# BQ25798.net
KiCad netlist of a schematic drawn in EAGLE
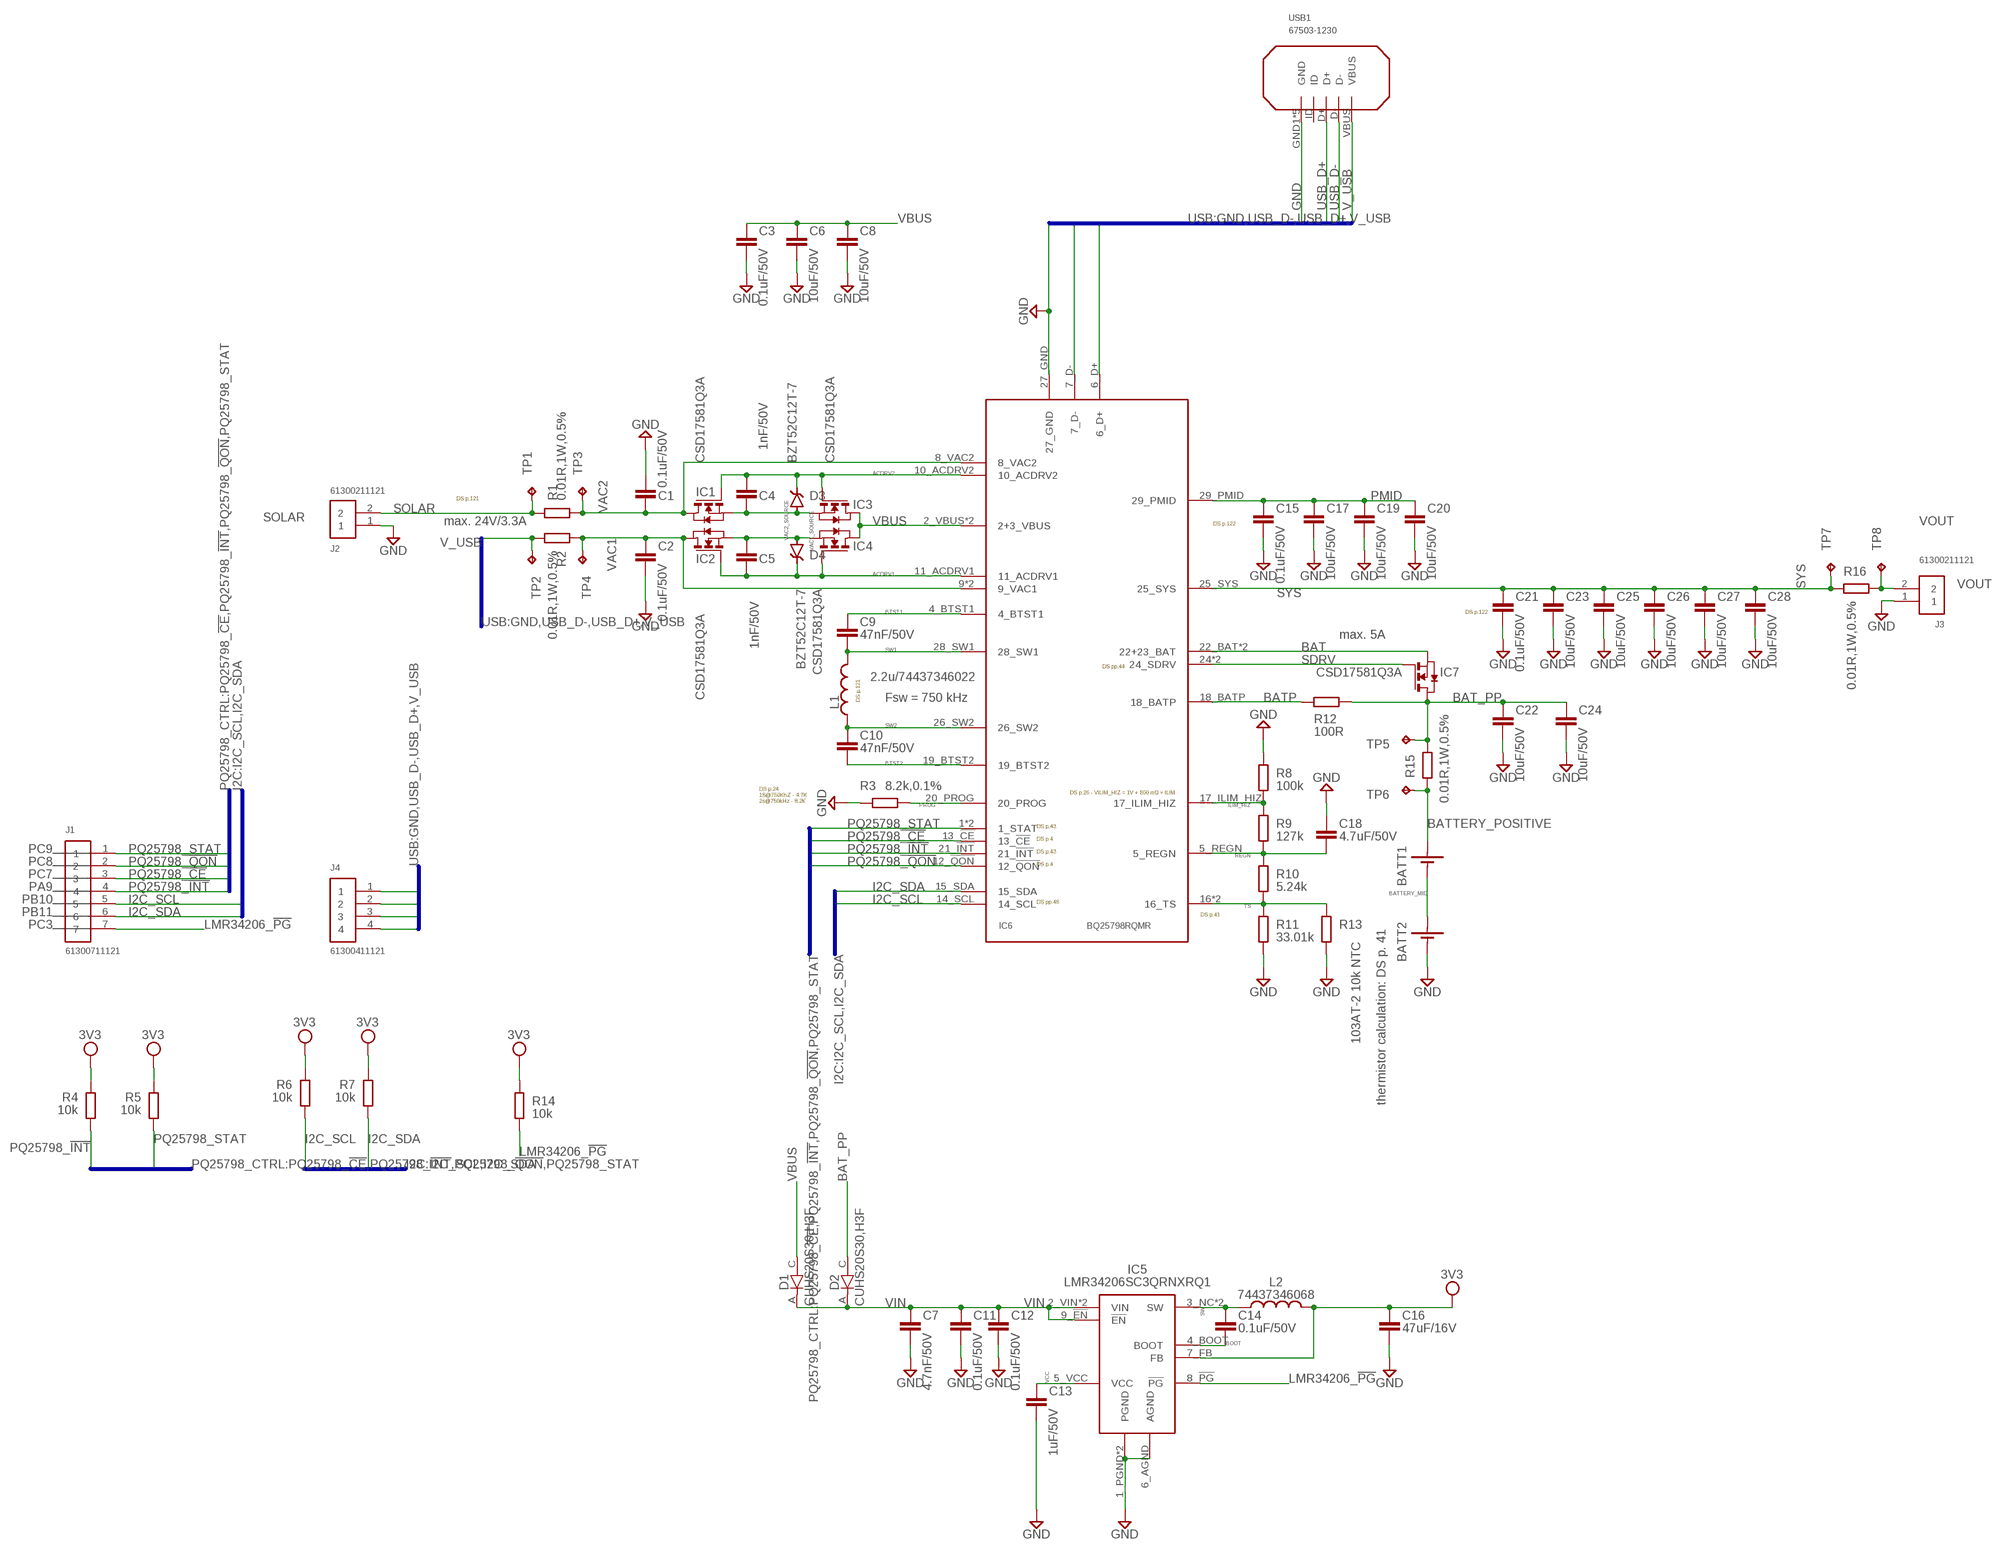
[diagram p0: schematic, sheet 1]

(export (version "E")
  (design (tool "Eeschema 10.0.6"))
  (components
    (comp (ref "BATT1")
      (value "BATTERY")
      (footprint "eagle-import:TH")
      (libsource (lib "eagle-import") (part "BATTERY"))
    )
    (comp (ref "BATT2")
      (value "BATTERY")
      (footprint "eagle-import:TH")
      (libsource (lib "eagle-import") (part "BATTERY"))
    )
    (comp (ref "C1")
      (value "0.1uF/50V")
      (footprint "eagle-import:C0402")
      (libsource (lib "eagle-import") (part "C-EUC0402"))
    )
    (comp (ref "C2")
      (value "0.1uF/50V")
      (footprint "eagle-import:C0402")
      (libsource (lib "eagle-import") (part "C-EUC0402"))
    )
    (comp (ref "C3")
      (value "0.1uF/50V")
      (footprint "eagle-import:C0402")
      (libsource (lib "eagle-import") (part "C-EUC0402"))
    )
    (comp (ref "C4")
      (value "1nF/50V")
      (footprint "eagle-import:C0402")
      (libsource (lib "eagle-import") (part "C-EUC0402"))
    )
    (comp (ref "C5")
      (value "1nF/50V")
      (footprint "eagle-import:C0402")
      (libsource (lib "eagle-import") (part "C-EUC0402"))
    )
    (comp (ref "C6")
      (value "10uF/50V")
      (footprint "eagle-import:C0805")
      (libsource (lib "eagle-import") (part "C-EUC0805"))
    )
    (comp (ref "C7")
      (value "4.7nF/50V")
      (footprint "eagle-import:C0805")
      (libsource (lib "eagle-import") (part "C-EUC0805"))
    )
    (comp (ref "C8")
      (value "10uF/50V")
      (footprint "eagle-import:C0805")
      (libsource (lib "eagle-import") (part "C-EUC0805"))
    )
    (comp (ref "C9")
      (value "47nF/50V")
      (footprint "eagle-import:C0603")
      (libsource (lib "eagle-import") (part "C-EUC0603"))
    )
    (comp (ref "C10")
      (value "47nF/50V")
      (footprint "eagle-import:C0603")
      (libsource (lib "eagle-import") (part "C-EUC0603"))
    )
    (comp (ref "C11")
      (value "0.1uF/50V")
      (footprint "eagle-import:C0402")
      (libsource (lib "eagle-import") (part "C-EUC0402"))
    )
    (comp (ref "C12")
      (value "0.1uF/50V")
      (footprint "eagle-import:C0402")
      (libsource (lib "eagle-import") (part "C-EUC0402"))
    )
    (comp (ref "C13")
      (value "1uF/50V")
      (footprint "eagle-import:C0805")
      (libsource (lib "eagle-import") (part "C-EUC0805"))
    )
    (comp (ref "C14")
      (value "0.1uF/50V")
      (footprint "eagle-import:C0402")
      (libsource (lib "eagle-import") (part "C-EUC0402"))
    )
    (comp (ref "C15")
      (value "0.1uF/50V")
      (footprint "eagle-import:C0402")
      (libsource (lib "eagle-import") (part "C-EUC0402"))
    )
    (comp (ref "C16")
      (value "47uF/16V")
      (footprint "eagle-import:C1206")
      (libsource (lib "eagle-import") (part "C-EUC1206"))
    )
    (comp (ref "C17")
      (value "10uF/50V")
      (footprint "eagle-import:C0805")
      (libsource (lib "eagle-import") (part "C-EUC0805"))
    )
    (comp (ref "C18")
      (value "4.7uF/50V")
      (footprint "eagle-import:C0603")
      (libsource (lib "eagle-import") (part "C-EUC0603"))
    )
    (comp (ref "C19")
      (value "10uF/50V")
      (footprint "eagle-import:C0805")
      (libsource (lib "eagle-import") (part "C-EUC0805"))
    )
    (comp (ref "C20")
      (value "10uF/50V")
      (footprint "eagle-import:C0805")
      (libsource (lib "eagle-import") (part "C-EUC0805"))
    )
    (comp (ref "C21")
      (value "0.1uF/50V")
      (footprint "eagle-import:C0402")
      (libsource (lib "eagle-import") (part "C-EUC0402"))
    )
    (comp (ref "C22")
      (value "10uF/50V")
      (footprint "eagle-import:C0805")
      (libsource (lib "eagle-import") (part "C-EUC0805"))
    )
    (comp (ref "C23")
      (value "10uF/50V")
      (footprint "eagle-import:C0805")
      (libsource (lib "eagle-import") (part "C-EUC0805"))
    )
    (comp (ref "C24")
      (value "10uF/50V")
      (footprint "eagle-import:C0805")
      (libsource (lib "eagle-import") (part "C-EUC0805"))
    )
    (comp (ref "C25")
      (value "10uF/50V")
      (footprint "eagle-import:C0805")
      (libsource (lib "eagle-import") (part "C-EUC0805"))
    )
    (comp (ref "C26")
      (value "10uF/50V")
      (footprint "eagle-import:C0805")
      (libsource (lib "eagle-import") (part "C-EUC0805"))
    )
    (comp (ref "C27")
      (value "10uF/50V")
      (footprint "eagle-import:C0805")
      (libsource (lib "eagle-import") (part "C-EUC0805"))
    )
    (comp (ref "C28")
      (value "10uF/50V")
      (footprint "eagle-import:C0805")
      (libsource (lib "eagle-import") (part "C-EUC0805"))
    )
    (comp (ref "D1")
      (value "CUHS20S30,H3F")
      (footprint "eagle-import:US2H")
      (libsource (lib "eagle-import") (part "CUHS20S30"))
    )
    (comp (ref "D2")
      (value "CUHS20S30,H3F")
      (footprint "eagle-import:US2H")
      (libsource (lib "eagle-import") (part "CUHS20S30"))
    )
    (comp (ref "D3")
      (value "BZT52C12T-7")
      (footprint "eagle-import:SOD-523-2")
      (libsource (lib "eagle-import") (part "BZT52C2V0T"))
    )
    (comp (ref "D4")
      (value "BZT52C12T-7")
      (footprint "eagle-import:SOD-523-2")
      (libsource (lib "eagle-import") (part "BZT52C2V0T"))
    )
    (comp (ref "IC1")
      (value "CSD17581Q3A")
      (footprint "eagle-import:PQFN-12")
      (libsource (lib "eagle-import") (part "CSD17581Q3A"))
    )
    (comp (ref "IC2")
      (value "CSD17581Q3A")
      (footprint "eagle-import:PQFN-12")
      (libsource (lib "eagle-import") (part "CSD17581Q3A"))
    )
    (comp (ref "IC3")
      (value "CSD17581Q3A")
      (footprint "eagle-import:PQFN-12")
      (libsource (lib "eagle-import") (part "CSD17581Q3A"))
    )
    (comp (ref "IC4")
      (value "CSD17581Q3A")
      (footprint "eagle-import:PQFN-12")
      (libsource (lib "eagle-import") (part "CSD17581Q3A"))
    )
    (comp (ref "IC5")
      (value "LMR34206SC3QRNXRQ1")
      (footprint "eagle-import:VQFN-HR(12)")
      (libsource (lib "eagle-import") (part "LMR34206-Q1"))
    )
    (comp (ref "IC6")
      (value "BQ25798RQMR")
      (footprint "eagle-import:QFN29")
      (libsource (lib "eagle-import") (part "BQ25798"))
    )
    (comp (ref "IC7")
      (value "CSD17581Q3A")
      (footprint "eagle-import:PQFN-12")
      (libsource (lib "eagle-import") (part "CSD17581Q3A"))
    )
    (comp (ref "J1")
      (value "61300711121")
      (footprint "eagle-import:61300711121")
      (fields
        (field (name "DIGI_KEY_PART_NUMBER") "732-5320-ND")
        (field (name "MANUFACTURER") "Wurth Electronics Inc.")
        (field (name "CREATED_BY") "PCBLayout.com")
      )
      (libsource (lib "eagle-import") (part "61300711121"))
    )
    (comp (ref "J2")
      (value "61300211121")
      (footprint "eagle-import:61300211121")
      (fields
        (field (name "DIGI_KEY_PART_NUMBER") "732-5315-ND")
        (field (name "MANUFACTURER") "Wurth Electronics Inc.")
        (field (name "CREATED_BY") "PCBLayout.com")
      )
      (libsource (lib "eagle-import") (part "61300211121"))
    )
    (comp (ref "J3")
      (value "61300211121")
      (footprint "eagle-import:61300211121")
      (fields
        (field (name "DIGI_KEY_PART_NUMBER") "732-5315-ND")
        (field (name "MANUFACTURER") "Wurth Electronics Inc.")
        (field (name "CREATED_BY") "PCBLayout.com")
      )
      (libsource (lib "eagle-import") (part "61300211121"))
    )
    (comp (ref "J4")
      (value "61300411121")
      (footprint "eagle-import:61300411121")
      (fields
        (field (name "DIGI_KEY_PART_NUMBER") "732-5317-ND")
        (field (name "MANUFACTURER") "Wurth Electronics Inc.")
        (field (name "CREATED_BY") "PCBLayout.com")
      )
      (libsource (lib "eagle-import") (part "61300411121"))
    )
    (comp (ref "L1")
      (value "2.2u/74437346022")
      (footprint "eagle-import:SMD")
      (libsource (lib "eagle-import") (part "74437346022"))
    )
    (comp (ref "L2")
      (value "74437346068")
      (footprint "eagle-import:SMD")
      (libsource (lib "eagle-import") (part "74437346022"))
    )
    (comp (ref "R1")
      (value "0.01R,1W,0.5%")
      (footprint "eagle-import:R1206")
      (libsource (lib "eagle-import") (part "R-EU_R1206"))
    )
    (comp (ref "R2")
      (value "0.01R,1W,0.5%")
      (footprint "eagle-import:R1206")
      (libsource (lib "eagle-import") (part "R-EU_R1206"))
    )
    (comp (ref "R3")
      (value "8.2k,0.1%")
      (footprint "eagle-import:R0603")
      (libsource (lib "eagle-import") (part "R-EU_R0603"))
    )
    (comp (ref "R4")
      (value "10k")
      (footprint "eagle-import:R0402")
      (libsource (lib "eagle-import") (part "R-EU_R0402"))
    )
    (comp (ref "R5")
      (value "10k")
      (footprint "eagle-import:R0402")
      (libsource (lib "eagle-import") (part "R-EU_R0402"))
    )
    (comp (ref "R6")
      (value "10k")
      (footprint "eagle-import:R0402")
      (libsource (lib "eagle-import") (part "R-EU_R0402"))
    )
    (comp (ref "R7")
      (value "10k")
      (footprint "eagle-import:R0402")
      (libsource (lib "eagle-import") (part "R-EU_R0402"))
    )
    (comp (ref "R8")
      (value "100k")
      (footprint "eagle-import:R0402")
      (libsource (lib "eagle-import") (part "R-EU_R0402"))
    )
    (comp (ref "R9")
      (value "127k")
      (footprint "eagle-import:R0402")
      (libsource (lib "eagle-import") (part "R-EU_R0402"))
    )
    (comp (ref "R10")
      (value "5.24k")
      (footprint "eagle-import:R0402")
      (libsource (lib "eagle-import") (part "R-EU_R0402"))
    )
    (comp (ref "R11")
      (value "33.01k")
      (footprint "eagle-import:R0402")
      (libsource (lib "eagle-import") (part "R-EU_R0402"))
    )
    (comp (ref "R12")
      (value "100R")
      (footprint "eagle-import:R0603")
      (libsource (lib "eagle-import") (part "R-EU_R0603"))
    )
    (comp (ref "R13")
      (value "103AT-2 10k NTC")
      (footprint "eagle-import:V526-0")
      (libsource (lib "eagle-import") (part "R-EU_V526-0"))
    )
    (comp (ref "R14")
      (value "10k")
      (footprint "eagle-import:R0402")
      (libsource (lib "eagle-import") (part "R-EU_R0402"))
    )
    (comp (ref "R15")
      (value "0.01R,1W,0.5%")
      (footprint "eagle-import:R1206")
      (libsource (lib "eagle-import") (part "R-EU_R1206"))
    )
    (comp (ref "R16")
      (value "0.01R,1W,0.5%")
      (footprint "eagle-import:R1206")
      (libsource (lib "eagle-import") (part "R-EU_R1206"))
    )
    (comp (ref "TP1")
      (value "TPPAD1-13")
      (footprint "eagle-import:P1-13")
      (libsource (lib "eagle-import") (part "TPPAD1-13"))
    )
    (comp (ref "TP2")
      (value "TPPAD1-13")
      (footprint "eagle-import:P1-13")
      (libsource (lib "eagle-import") (part "TPPAD1-13"))
    )
    (comp (ref "TP3")
      (value "TPPAD1-13")
      (footprint "eagle-import:P1-13")
      (libsource (lib "eagle-import") (part "TPPAD1-13"))
    )
    (comp (ref "TP4")
      (value "TPPAD1-13")
      (footprint "eagle-import:P1-13")
      (libsource (lib "eagle-import") (part "TPPAD1-13"))
    )
    (comp (ref "TP5")
      (value "TPPAD1-13")
      (footprint "eagle-import:P1-13")
      (libsource (lib "eagle-import") (part "TPPAD1-13"))
    )
    (comp (ref "TP6")
      (value "TPPAD1-13")
      (footprint "eagle-import:P1-13")
      (libsource (lib "eagle-import") (part "TPPAD1-13"))
    )
    (comp (ref "TP7")
      (value "TPPAD1-13")
      (footprint "eagle-import:P1-13")
      (libsource (lib "eagle-import") (part "TPPAD1-13"))
    )
    (comp (ref "TP8")
      (value "TPPAD1-13")
      (footprint "eagle-import:P1-13")
      (libsource (lib "eagle-import") (part "TPPAD1-13"))
    )
    (comp (ref "USB1")
      (value "67503-1230")
      (footprint "eagle-import:SMT")
      (libsource (lib "eagle-import") (part "MX-67503-1230"))
    )
  )
  (nets
    (net (code "4") (name "/ACDRV1") (class "Default")
      (node (ref "C5") (pin "2") (pinfunction "2_2") (pintype "passive"))
      (node (ref "D4") (pin "C") (pinfunction "C_C") (pintype "passive"))
      (node (ref "IC2") (pin "4_G") (pinfunction "G_4_G") (pintype "passive"))
      (node (ref "IC4") (pin "4_G") (pinfunction "G_4_G") (pintype "passive"))
      (node (ref "IC6") (pin "11_ACDRV1") (pinfunction "11_ACDRV1_11_ACDRV1") (pintype "output"))
    )
    (net (code "5") (name "/ACDRV2") (class "Default")
      (node (ref "C4") (pin "1") (pinfunction "1_1") (pintype "passive"))
      (node (ref "D3") (pin "C") (pinfunction "C_C") (pintype "passive"))
      (node (ref "IC1") (pin "4_G") (pinfunction "G_4_G") (pintype "passive"))
      (node (ref "IC3") (pin "4_G") (pinfunction "G_4_G") (pintype "passive"))
      (node (ref "IC6") (pin "10_ACDRV2") (pinfunction "10_ACDRV2_10_ACDRV2") (pintype "output"))
    )
    (net (code "6") (name "/BAT") (class "Default")
      (node (ref "IC6") (pin "22_BAT") (pinfunction "22+23_BAT_22_BAT") (pintype "power_in"))
      (node (ref "IC6") (pin "23_BAT") (pinfunction "22+23_BAT_23_BAT") (pintype "power_in"))
      (node (ref "IC7") (pin "1_S") (pinfunction "S_1_S") (pintype "passive"))
      (node (ref "IC7") (pin "2_S") (pinfunction "S_2_S") (pintype "passive"))
      (node (ref "IC7") (pin "3_S") (pinfunction "S_3_S") (pintype "passive"))
    )
    (net (code "7") (name "/BATP") (class "Default")
      (node (ref "IC6") (pin "18_BATP") (pinfunction "18_BATP_18_BATP") (pintype "power_in"))
      (node (ref "R12") (pin "1") (pinfunction "1_1") (pintype "passive"))
    )
    (net (code "8") (name "/BATTERY_MID") (class "Default")
      (node (ref "BATT1") (pin "-") (pinfunction "NEG_-") (pintype "power_in"))
      (node (ref "BATT2") (pin "+") (pinfunction "POS_+") (pintype "power_in"))
    )
    (net (code "9") (name "/BATTERY_POSITIVE") (class "Default")
      (node (ref "BATT1") (pin "+") (pinfunction "POS_+") (pintype "power_in"))
      (node (ref "R15") (pin "1") (pinfunction "1_1") (pintype "passive"))
      (node (ref "TP6") (pin "TP") (pinfunction "TP_TP") (pintype "input"))
    )
    (net (code "10") (name "/BAT_PP") (class "Default")
      (node (ref "C22") (pin "1") (pinfunction "1_1") (pintype "passive"))
      (node (ref "C24") (pin "1") (pinfunction "1_1") (pintype "passive"))
      (node (ref "D2") (pin "C") (pinfunction "C_C") (pintype "bidirectional"))
      (node (ref "IC7") (pin "5_D") (pinfunction "D_5_D") (pintype "passive"))
      (node (ref "IC7") (pin "6_D") (pinfunction "D_6_D") (pintype "passive"))
      (node (ref "IC7") (pin "7_D") (pinfunction "D_7_D") (pintype "passive"))
      (node (ref "IC7") (pin "8_D") (pinfunction "D_8_D") (pintype "passive"))
      (node (ref "IC7") (pin "9_D") (pinfunction "D_9_D") (pintype "passive"))
      (node (ref "R12") (pin "2") (pinfunction "2_2") (pintype "passive"))
      (node (ref "R15") (pin "2") (pinfunction "2_2") (pintype "passive"))
      (node (ref "TP5") (pin "TP") (pinfunction "TP_TP") (pintype "input"))
    )
    (net (code "11") (name "/BOOT") (class "Default")
      (node (ref "C14") (pin "2") (pinfunction "2_2") (pintype "passive"))
      (node (ref "IC5") (pin "4_BOOT") (pinfunction "BOOT_4_BOOT") (pintype "bidirectional"))
    )
    (net (code "12") (name "/BTST1") (class "Default")
      (node (ref "C9") (pin "1") (pinfunction "1_1") (pintype "passive"))
      (node (ref "IC6") (pin "4_BTST1") (pinfunction "4_BTST1_4_BTST1") (pintype "output"))
    )
    (net (code "13") (name "/BTST2") (class "Default")
      (node (ref "C10") (pin "2") (pinfunction "2_2") (pintype "passive"))
      (node (ref "IC6") (pin "19_BTST2") (pinfunction "19_BTST2_19_BTST2") (pintype "output"))
    )
    (net (code "14") (name "/I2C_SCL") (class "Default")
      (node (ref "IC6") (pin "14_SCL") (pinfunction "14_SCL_14_SCL") (pintype "input"))
      (node (ref "J1") (pin "5") (pinfunction "5_5") (pintype "passive"))
      (node (ref "R6") (pin "1") (pinfunction "1_1") (pintype "passive"))
    )
    (net (code "15") (name "/I2C_SDA") (class "Default")
      (node (ref "IC6") (pin "15_SDA") (pinfunction "15_SDA_15_SDA") (pintype "bidirectional"))
      (node (ref "J1") (pin "6") (pinfunction "6_6") (pintype "passive"))
      (node (ref "R7") (pin "1") (pinfunction "1_1") (pintype "passive"))
    )
    (net (code "16") (name "/ILIM_HIZ") (class "Default")
      (node (ref "IC6") (pin "17_ILIM_HIZ") (pinfunction "17_ILIM_HIZ_17_ILIM_HIZ") (pintype "input"))
      (node (ref "R8") (pin "2") (pinfunction "2_2") (pintype "passive"))
      (node (ref "R9") (pin "1") (pinfunction "1_1") (pintype "passive"))
    )
    (net (code "17") (name "/LMR34206_~{PG}") (class "Default")
      (node (ref "IC5") (pin "8_!PG!") (pinfunction "~{PG}_8_!PG!") (pintype "output"))
      (node (ref "J1") (pin "7") (pinfunction "7_7") (pintype "passive"))
      (node (ref "R14") (pin "2") (pinfunction "2_2") (pintype "passive"))
    )
    (net (code "18") (name "/PMID") (class "Default")
      (node (ref "C15") (pin "1") (pinfunction "1_1") (pintype "passive"))
      (node (ref "C17") (pin "1") (pinfunction "1_1") (pintype "passive"))
      (node (ref "C19") (pin "1") (pinfunction "1_1") (pintype "passive"))
      (node (ref "C20") (pin "1") (pinfunction "1_1") (pintype "passive"))
      (node (ref "IC6") (pin "29_PMID") (pinfunction "29_PMID_29_PMID") (pintype "output"))
    )
    (net (code "19") (name "/PQ25798_STAT") (class "Default")
      (node (ref "IC6") (pin "1") (pinfunction "1_STAT_1") (pintype "output"))
      (node (ref "IC6") (pin "1_STAT") (pinfunction "1_STAT_1_STAT") (pintype "output"))
      (node (ref "J1") (pin "1") (pinfunction "1_1") (pintype "passive"))
      (node (ref "R5") (pin "1") (pinfunction "1_1") (pintype "passive"))
    )
    (net (code "20") (name "/PQ25798_~{CE}") (class "Default")
      (node (ref "IC6") (pin "13_!CE!") (pinfunction "13_~{CE}_13_!CE!") (pintype "input"))
      (node (ref "J1") (pin "3") (pinfunction "3_3") (pintype "passive"))
    )
    (net (code "21") (name "/PQ25798_~{INT}") (class "Default")
      (node (ref "IC6") (pin "21_!INT!") (pinfunction "21_~{INT}_21_!INT!") (pintype "output"))
      (node (ref "J1") (pin "4") (pinfunction "4_4") (pintype "passive"))
      (node (ref "R4") (pin "1") (pinfunction "1_1") (pintype "passive"))
    )
    (net (code "22") (name "/PQ25798_~{QON}") (class "Default")
      (node (ref "IC6") (pin "12_!QON!") (pinfunction "12_~{QON}_12_!QON!") (pintype "input"))
      (node (ref "J1") (pin "2") (pinfunction "2_2") (pintype "passive"))
    )
    (net (code "23") (name "/PROG") (class "Default")
      (node (ref "IC6") (pin "20_PROG") (pinfunction "20_PROG_20_PROG") (pintype "input"))
      (node (ref "R3") (pin "2") (pinfunction "2_2") (pintype "passive"))
    )
    (net (code "24") (name "/REGN") (class "Default")
      (node (ref "C18") (pin "2") (pinfunction "2_2") (pintype "passive"))
      (node (ref "IC6") (pin "5_REGN") (pinfunction "5_REGN_5_REGN") (pintype "output"))
      (node (ref "R10") (pin "1") (pinfunction "1_1") (pintype "passive"))
      (node (ref "R9") (pin "2") (pinfunction "2_2") (pintype "passive"))
    )
    (net (code "25") (name "/SDRV") (class "Default")
      (node (ref "IC6") (pin "24") (pinfunction "24_SDRV_24") (pintype "output"))
      (node (ref "IC6") (pin "24_SDRV") (pinfunction "24_SDRV_24_SDRV") (pintype "output"))
      (node (ref "IC7") (pin "4_G") (pinfunction "G_4_G") (pintype "passive"))
    )
    (net (code "26") (name "/SOLAR") (class "Default")
      (node (ref "J2") (pin "2") (pinfunction "2_2") (pintype "passive"))
      (node (ref "R1") (pin "1") (pinfunction "1_1") (pintype "passive"))
      (node (ref "TP1") (pin "TP") (pinfunction "TP_TP") (pintype "input"))
    )
    (net (code "27") (name "/SW") (class "Default")
      (node (ref "C14") (pin "1") (pinfunction "1_1") (pintype "passive"))
      (node (ref "IC5") (pin "12_SW") (pinfunction "SW_12_SW") (pintype "bidirectional"))
      (node (ref "IC5") (pin "3_NC") (pinfunction "SW_3_NC") (pintype "bidirectional"))
      (node (ref "L2") (pin "P$1") (pinfunction "P$1_P$1") (pintype "bidirectional"))
    )
    (net (code "28") (name "/SW1") (class "Default")
      (node (ref "C9") (pin "2") (pinfunction "2_2") (pintype "passive"))
      (node (ref "IC6") (pin "28_SW1") (pinfunction "28_SW1_28_SW1") (pintype "power_in"))
      (node (ref "L1") (pin "P$2") (pinfunction "P$2_P$2") (pintype "bidirectional"))
    )
    (net (code "29") (name "/SW2") (class "Default")
      (node (ref "C10") (pin "1") (pinfunction "1_1") (pintype "passive"))
      (node (ref "IC6") (pin "26_SW2") (pinfunction "26_SW2_26_SW2") (pintype "power_in"))
      (node (ref "L1") (pin "P$1") (pinfunction "P$1_P$1") (pintype "bidirectional"))
    )
    (net (code "30") (name "/SYS") (class "Default")
      (node (ref "C21") (pin "1") (pinfunction "1_1") (pintype "passive"))
      (node (ref "C23") (pin "1") (pinfunction "1_1") (pintype "passive"))
      (node (ref "C25") (pin "1") (pinfunction "1_1") (pintype "passive"))
      (node (ref "C26") (pin "1") (pinfunction "1_1") (pintype "passive"))
      (node (ref "C27") (pin "1") (pinfunction "1_1") (pintype "passive"))
      (node (ref "C28") (pin "1") (pinfunction "1_1") (pintype "passive"))
      (node (ref "IC6") (pin "25_SYS") (pinfunction "25_SYS_25_SYS") (pintype "power_in"))
      (node (ref "R16") (pin "1") (pinfunction "1_1") (pintype "passive"))
      (node (ref "TP7") (pin "TP") (pinfunction "TP_TP") (pintype "input"))
    )
    (net (code "31") (name "/TS") (class "Default")
      (node (ref "IC6") (pin "16") (pinfunction "16_TS_16") (pintype "input"))
      (node (ref "IC6") (pin "16_TS") (pinfunction "16_TS_16_TS") (pintype "input"))
      (node (ref "R10") (pin "2") (pinfunction "2_2") (pintype "passive"))
      (node (ref "R11") (pin "1") (pinfunction "1_1") (pintype "passive"))
      (node (ref "R13") (pin "1") (pinfunction "1_1") (pintype "passive"))
    )
    (net (code "32") (name "/USB_D+") (class "Default")
      (node (ref "IC6") (pin "6_D+") (pinfunction "6_D+_6_D+") (pintype "bidirectional"))
      (node (ref "J4") (pin "2") (pinfunction "2_2") (pintype "passive"))
      (node (ref "USB1") (pin "D+") (pinfunction "D+_D+") (pintype "bidirectional"))
    )
    (net (code "33") (name "/USB_D-") (class "Default")
      (node (ref "IC6") (pin "7_D-") (pinfunction "7_D-_7_D-") (pintype "bidirectional"))
      (node (ref "J4") (pin "3") (pinfunction "3_3") (pintype "passive"))
      (node (ref "USB1") (pin "D-") (pinfunction "D-_D-") (pintype "bidirectional"))
    )
    (net (code "34") (name "/VAC1") (class "Default")
      (node (ref "C2") (pin "1") (pinfunction "1_1") (pintype "passive"))
      (node (ref "IC2") (pin "5_D") (pinfunction "D_5_D") (pintype "passive"))
      (node (ref "IC2") (pin "6_D") (pinfunction "D_6_D") (pintype "passive"))
      (node (ref "IC2") (pin "7_D") (pinfunction "D_7_D") (pintype "passive"))
      (node (ref "IC2") (pin "8_D") (pinfunction "D_8_D") (pintype "passive"))
      (node (ref "IC2") (pin "9_D") (pinfunction "D_9_D") (pintype "passive"))
      (node (ref "IC6") (pin "9") (pinfunction "9_VAC1_9") (pintype "input"))
      (node (ref "IC6") (pin "9_VAC1") (pinfunction "9_VAC1_9_VAC1") (pintype "input"))
      (node (ref "R2") (pin "2") (pinfunction "2_2") (pintype "passive"))
      (node (ref "TP4") (pin "TP") (pinfunction "TP_TP") (pintype "input"))
    )
    (net (code "35") (name "/VAC1_SOURCE") (class "Default")
      (node (ref "C5") (pin "1") (pinfunction "1_1") (pintype "passive"))
      (node (ref "D4") (pin "A") (pinfunction "A_A") (pintype "passive"))
      (node (ref "IC2") (pin "1_S") (pinfunction "S_1_S") (pintype "passive"))
      (node (ref "IC2") (pin "2_S") (pinfunction "S_2_S") (pintype "passive"))
      (node (ref "IC2") (pin "3_S") (pinfunction "S_3_S") (pintype "passive"))
      (node (ref "IC4") (pin "1_S") (pinfunction "S_1_S") (pintype "passive"))
      (node (ref "IC4") (pin "2_S") (pinfunction "S_2_S") (pintype "passive"))
      (node (ref "IC4") (pin "3_S") (pinfunction "S_3_S") (pintype "passive"))
    )
    (net (code "36") (name "/VAC2") (class "Default")
      (node (ref "C1") (pin "2") (pinfunction "2_2") (pintype "passive"))
      (node (ref "IC1") (pin "5_D") (pinfunction "D_5_D") (pintype "passive"))
      (node (ref "IC1") (pin "6_D") (pinfunction "D_6_D") (pintype "passive"))
      (node (ref "IC1") (pin "7_D") (pinfunction "D_7_D") (pintype "passive"))
      (node (ref "IC1") (pin "8_D") (pinfunction "D_8_D") (pintype "passive"))
      (node (ref "IC1") (pin "9_D") (pinfunction "D_9_D") (pintype "passive"))
      (node (ref "IC6") (pin "8_VAC2") (pinfunction "8_VAC2_8_VAC2") (pintype "input"))
      (node (ref "R1") (pin "2") (pinfunction "2_2") (pintype "passive"))
      (node (ref "TP3") (pin "TP") (pinfunction "TP_TP") (pintype "input"))
    )
    (net (code "37") (name "/VAC2_SOURCE") (class "Default")
      (node (ref "C4") (pin "2") (pinfunction "2_2") (pintype "passive"))
      (node (ref "D3") (pin "A") (pinfunction "A_A") (pintype "passive"))
      (node (ref "IC1") (pin "1_S") (pinfunction "S_1_S") (pintype "passive"))
      (node (ref "IC1") (pin "2_S") (pinfunction "S_2_S") (pintype "passive"))
      (node (ref "IC1") (pin "3_S") (pinfunction "S_3_S") (pintype "passive"))
      (node (ref "IC3") (pin "1_S") (pinfunction "S_1_S") (pintype "passive"))
      (node (ref "IC3") (pin "2_S") (pinfunction "S_2_S") (pintype "passive"))
      (node (ref "IC3") (pin "3_S") (pinfunction "S_3_S") (pintype "passive"))
    )
    (net (code "38") (name "/VBUS") (class "Default")
      (node (ref "C3") (pin "1") (pinfunction "1_1") (pintype "passive"))
      (node (ref "C6") (pin "1") (pinfunction "1_1") (pintype "passive"))
      (node (ref "C8") (pin "1") (pinfunction "1_1") (pintype "passive"))
      (node (ref "D1") (pin "C") (pinfunction "C_C") (pintype "bidirectional"))
      (node (ref "IC3") (pin "5_D") (pinfunction "D_5_D") (pintype "passive"))
      (node (ref "IC3") (pin "6_D") (pinfunction "D_6_D") (pintype "passive"))
      (node (ref "IC3") (pin "7_D") (pinfunction "D_7_D") (pintype "passive"))
      (node (ref "IC3") (pin "8_D") (pinfunction "D_8_D") (pintype "passive"))
      (node (ref "IC3") (pin "9_D") (pinfunction "D_9_D") (pintype "passive"))
      (node (ref "IC4") (pin "5_D") (pinfunction "D_5_D") (pintype "passive"))
      (node (ref "IC4") (pin "6_D") (pinfunction "D_6_D") (pintype "passive"))
      (node (ref "IC4") (pin "7_D") (pinfunction "D_7_D") (pintype "passive"))
      (node (ref "IC4") (pin "8_D") (pinfunction "D_8_D") (pintype "passive"))
      (node (ref "IC4") (pin "9_D") (pinfunction "D_9_D") (pintype "passive"))
      (node (ref "IC6") (pin "2_VBUS") (pinfunction "2+3_VBUS_2_VBUS") (pintype "power_in"))
      (node (ref "IC6") (pin "3_VBUS") (pinfunction "2+3_VBUS_3_VBUS") (pintype "power_in"))
    )
    (net (code "39") (name "/VCC") (class "Default")
      (node (ref "C13") (pin "1") (pinfunction "1_1") (pintype "passive"))
      (node (ref "IC5") (pin "5_VCC") (pinfunction "VCC_5_VCC") (pintype "power_in"))
    )
    (net (code "40") (name "/VIN") (class "Default")
      (node (ref "C11") (pin "1") (pinfunction "1_1") (pintype "passive"))
      (node (ref "C12") (pin "1") (pinfunction "1_1") (pintype "passive"))
      (node (ref "C7") (pin "1") (pinfunction "1_1") (pintype "passive"))
      (node (ref "D1") (pin "A") (pinfunction "A_A") (pintype "bidirectional"))
      (node (ref "D2") (pin "A") (pinfunction "A_A") (pintype "bidirectional"))
      (node (ref "IC5") (pin "10_VIN") (pinfunction "VIN_10_VIN") (pintype "power_in"))
      (node (ref "IC5") (pin "2_VIN") (pinfunction "VIN_2_VIN") (pintype "power_in"))
      (node (ref "IC5") (pin "9_!EN!") (pinfunction "~{EN}_9_!EN!") (pintype "input"))
    )
    (net (code "41") (name "/VOUT") (class "Default")
      (node (ref "J3") (pin "2") (pinfunction "2_2") (pintype "passive"))
      (node (ref "R16") (pin "2") (pinfunction "2_2") (pintype "passive"))
      (node (ref "TP8") (pin "TP") (pinfunction "TP_TP") (pintype "input"))
    )
    (net (code "42") (name "/V_USB") (class "Default")
      (node (ref "J4") (pin "4") (pinfunction "4_4") (pintype "passive"))
      (node (ref "R2") (pin "1") (pinfunction "1_1") (pintype "passive"))
      (node (ref "TP2") (pin "TP") (pinfunction "TP_TP") (pintype "input"))
      (node (ref "USB1") (pin "VBUS") (pinfunction "VBUS_VBUS") (pintype "power_in"))
    )
    (net (code "46") (name "3V3") (class "Default")
      (node (ref "C16") (pin "1") (pinfunction "1_1") (pintype "passive"))
      (node (ref "IC5") (pin "7_FB") (pinfunction "FB_7_FB") (pintype "bidirectional"))
      (node (ref "L2") (pin "P$2") (pinfunction "P$2_P$2") (pintype "bidirectional"))
      (node (ref "R14") (pin "1") (pinfunction "1_1") (pintype "passive"))
      (node (ref "R4") (pin "2") (pinfunction "2_2") (pintype "passive"))
      (node (ref "R5") (pin "2") (pinfunction "2_2") (pintype "passive"))
      (node (ref "R6") (pin "2") (pinfunction "2_2") (pintype "passive"))
      (node (ref "R7") (pin "2") (pinfunction "2_2") (pintype "passive"))
    )
    (net (code "47") (name "GND") (class "Default")
      (node (ref "BATT2") (pin "-") (pinfunction "NEG_-") (pintype "power_in"))
      (node (ref "C1") (pin "1") (pinfunction "1_1") (pintype "passive"))
      (node (ref "C11") (pin "2") (pinfunction "2_2") (pintype "passive"))
      (node (ref "C12") (pin "2") (pinfunction "2_2") (pintype "passive"))
      (node (ref "C13") (pin "2") (pinfunction "2_2") (pintype "passive"))
      (node (ref "C15") (pin "2") (pinfunction "2_2") (pintype "passive"))
      (node (ref "C16") (pin "2") (pinfunction "2_2") (pintype "passive"))
      (node (ref "C17") (pin "2") (pinfunction "2_2") (pintype "passive"))
      (node (ref "C18") (pin "1") (pinfunction "1_1") (pintype "passive"))
      (node (ref "C19") (pin "2") (pinfunction "2_2") (pintype "passive"))
      (node (ref "C2") (pin "2") (pinfunction "2_2") (pintype "passive"))
      (node (ref "C20") (pin "2") (pinfunction "2_2") (pintype "passive"))
      (node (ref "C21") (pin "2") (pinfunction "2_2") (pintype "passive"))
      (node (ref "C22") (pin "2") (pinfunction "2_2") (pintype "passive"))
      (node (ref "C23") (pin "2") (pinfunction "2_2") (pintype "passive"))
      (node (ref "C24") (pin "2") (pinfunction "2_2") (pintype "passive"))
      (node (ref "C25") (pin "2") (pinfunction "2_2") (pintype "passive"))
      (node (ref "C26") (pin "2") (pinfunction "2_2") (pintype "passive"))
      (node (ref "C27") (pin "2") (pinfunction "2_2") (pintype "passive"))
      (node (ref "C28") (pin "2") (pinfunction "2_2") (pintype "passive"))
      (node (ref "C3") (pin "2") (pinfunction "2_2") (pintype "passive"))
      (node (ref "C6") (pin "2") (pinfunction "2_2") (pintype "passive"))
      (node (ref "C7") (pin "2") (pinfunction "2_2") (pintype "passive"))
      (node (ref "C8") (pin "2") (pinfunction "2_2") (pintype "passive"))
      (node (ref "IC5") (pin "11_PGND") (pinfunction "PGND_11_PGND") (pintype "power_in"))
      (node (ref "IC5") (pin "1_PGND") (pinfunction "PGND_1_PGND") (pintype "power_in"))
      (node (ref "IC5") (pin "6_AGND") (pinfunction "AGND_6_AGND") (pintype "power_in"))
      (node (ref "IC6") (pin "27_GND") (pinfunction "27_GND_27_GND") (pintype "power_in"))
      (node (ref "J2") (pin "1") (pinfunction "1_1") (pintype "passive"))
      (node (ref "J3") (pin "1") (pinfunction "1_1") (pintype "passive"))
      (node (ref "J4") (pin "1") (pinfunction "1_1") (pintype "passive"))
      (node (ref "R11") (pin "2") (pinfunction "2_2") (pintype "passive"))
      (node (ref "R13") (pin "2") (pinfunction "2_2") (pintype "passive"))
      (node (ref "R3") (pin "1") (pinfunction "1_1") (pintype "passive"))
      (node (ref "R8") (pin "1") (pinfunction "1_1") (pintype "passive"))
      (node (ref "USB1") (pin "GND1") (pinfunction "GND_GND1") (pintype "power_in"))
      (node (ref "USB1") (pin "GND2") (pinfunction "GND_GND2") (pintype "power_in"))
      (node (ref "USB1") (pin "GND3") (pinfunction "GND_GND3") (pintype "power_in"))
      (node (ref "USB1") (pin "GND4") (pinfunction "GND_GND4") (pintype "power_in"))
      (node (ref "USB1") (pin "GND5") (pinfunction "GND_GND5") (pintype "power_in"))
    )
    (net (code "48") (name "unconnected-(USB1-PadID)") (class "Default")
      (node (ref "USB1") (pin "ID") (pinfunction "ID_ID") (pintype "bidirectional"))
    )
  )
)
